# M8340E.net
KiCad netlist of a schematic drawn in EAGLE
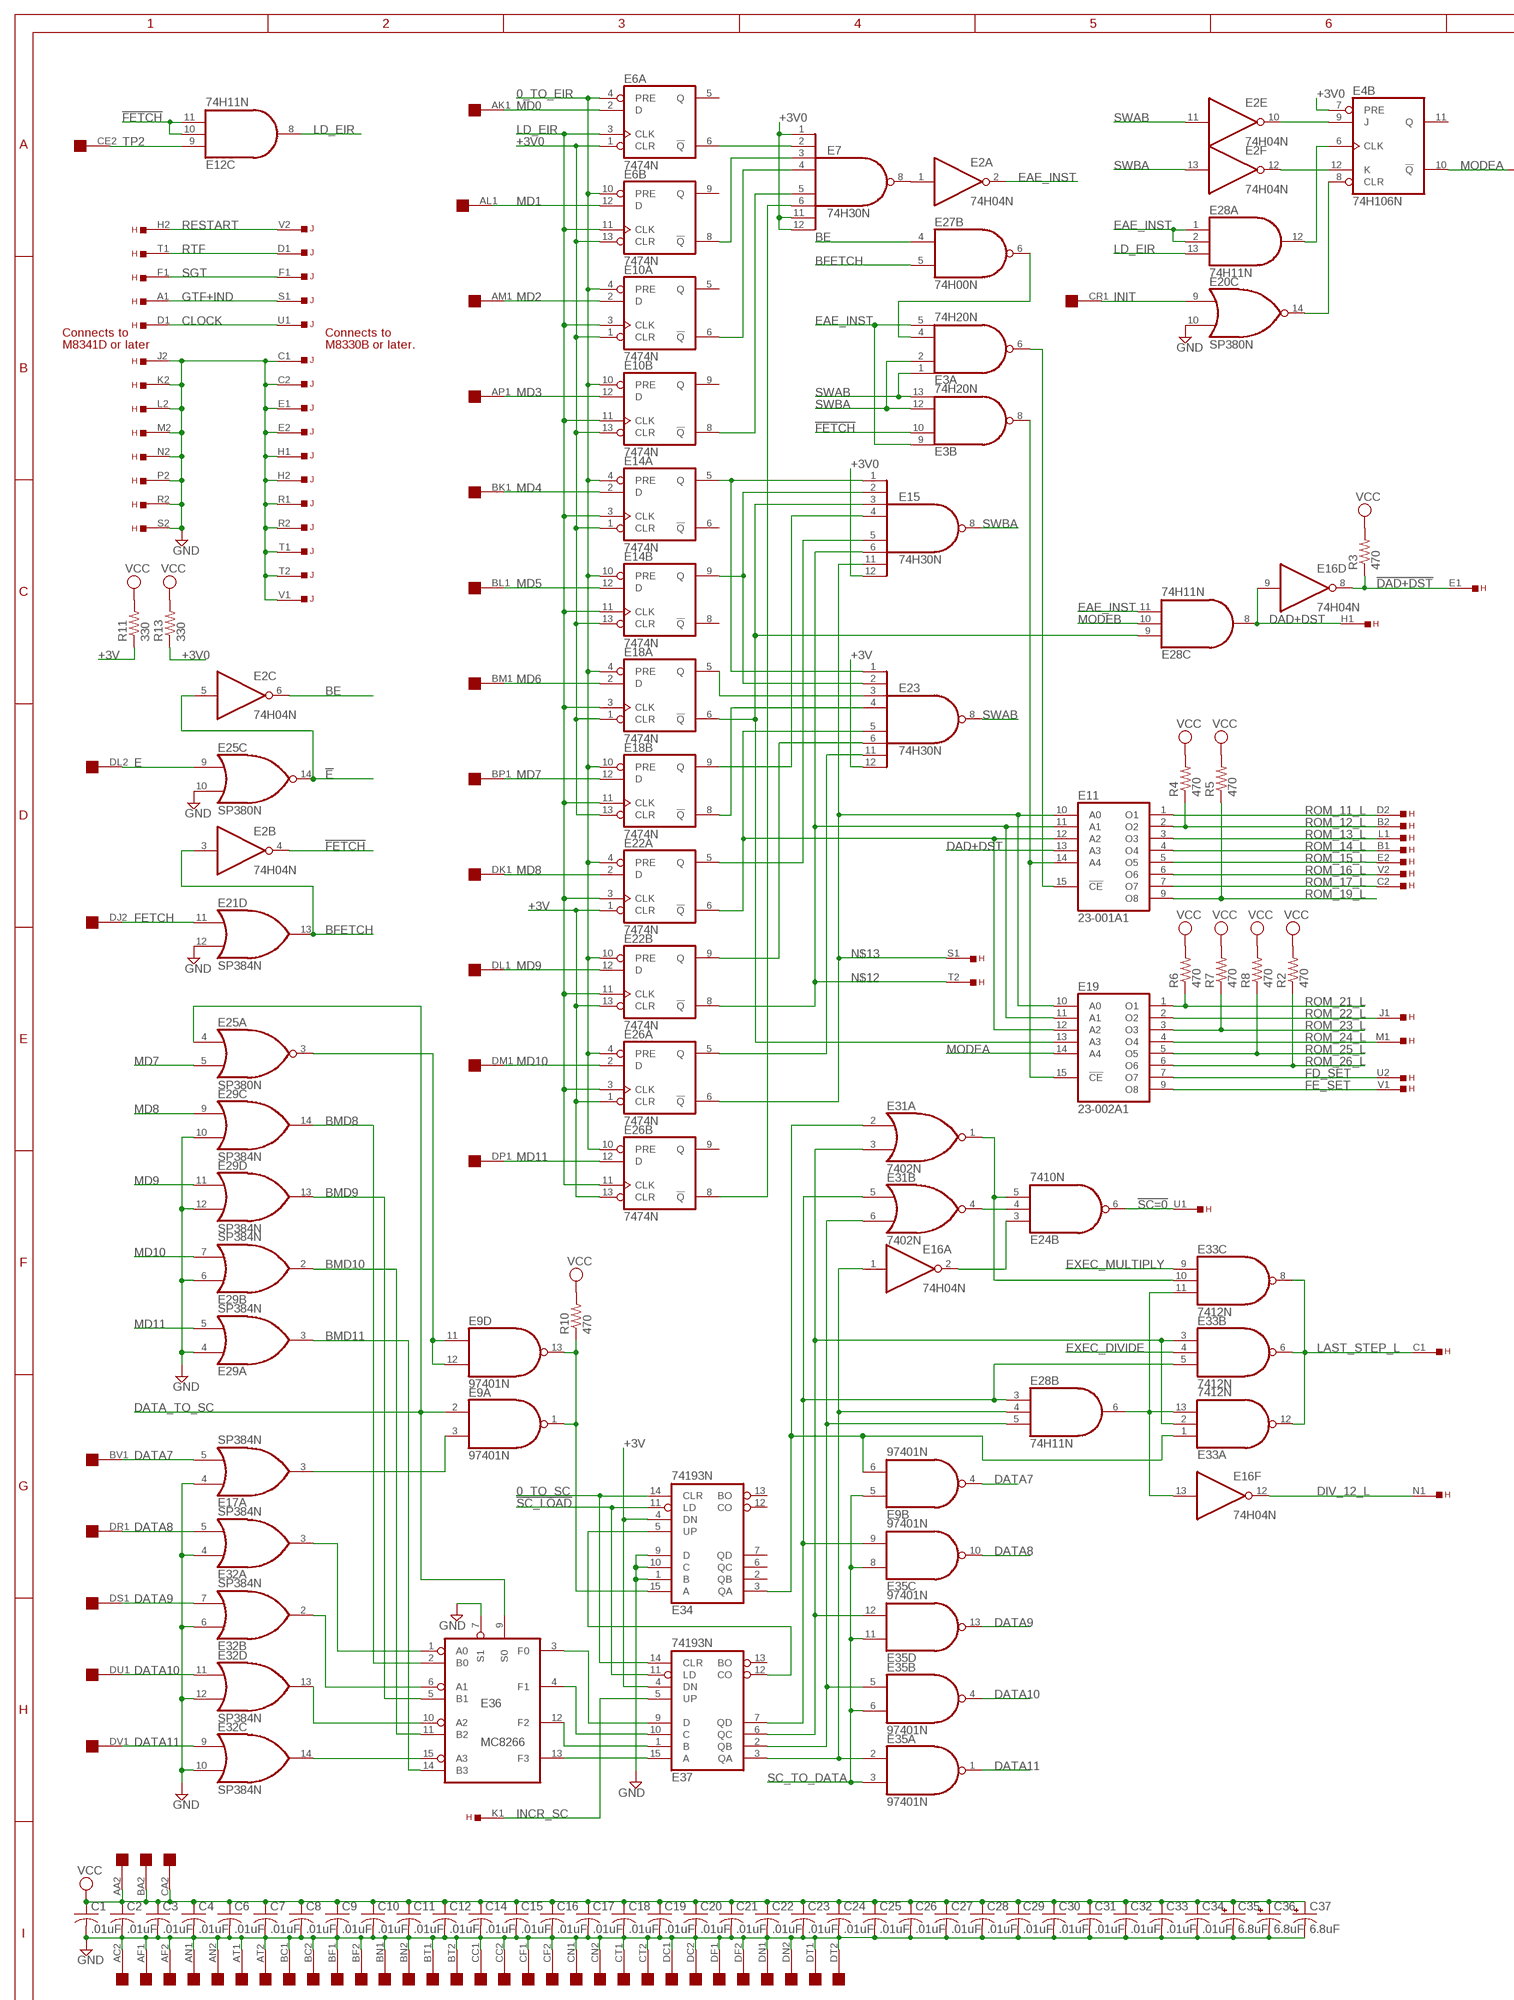
[diagram p0: schematic, sheet 1, part 1 of 2]
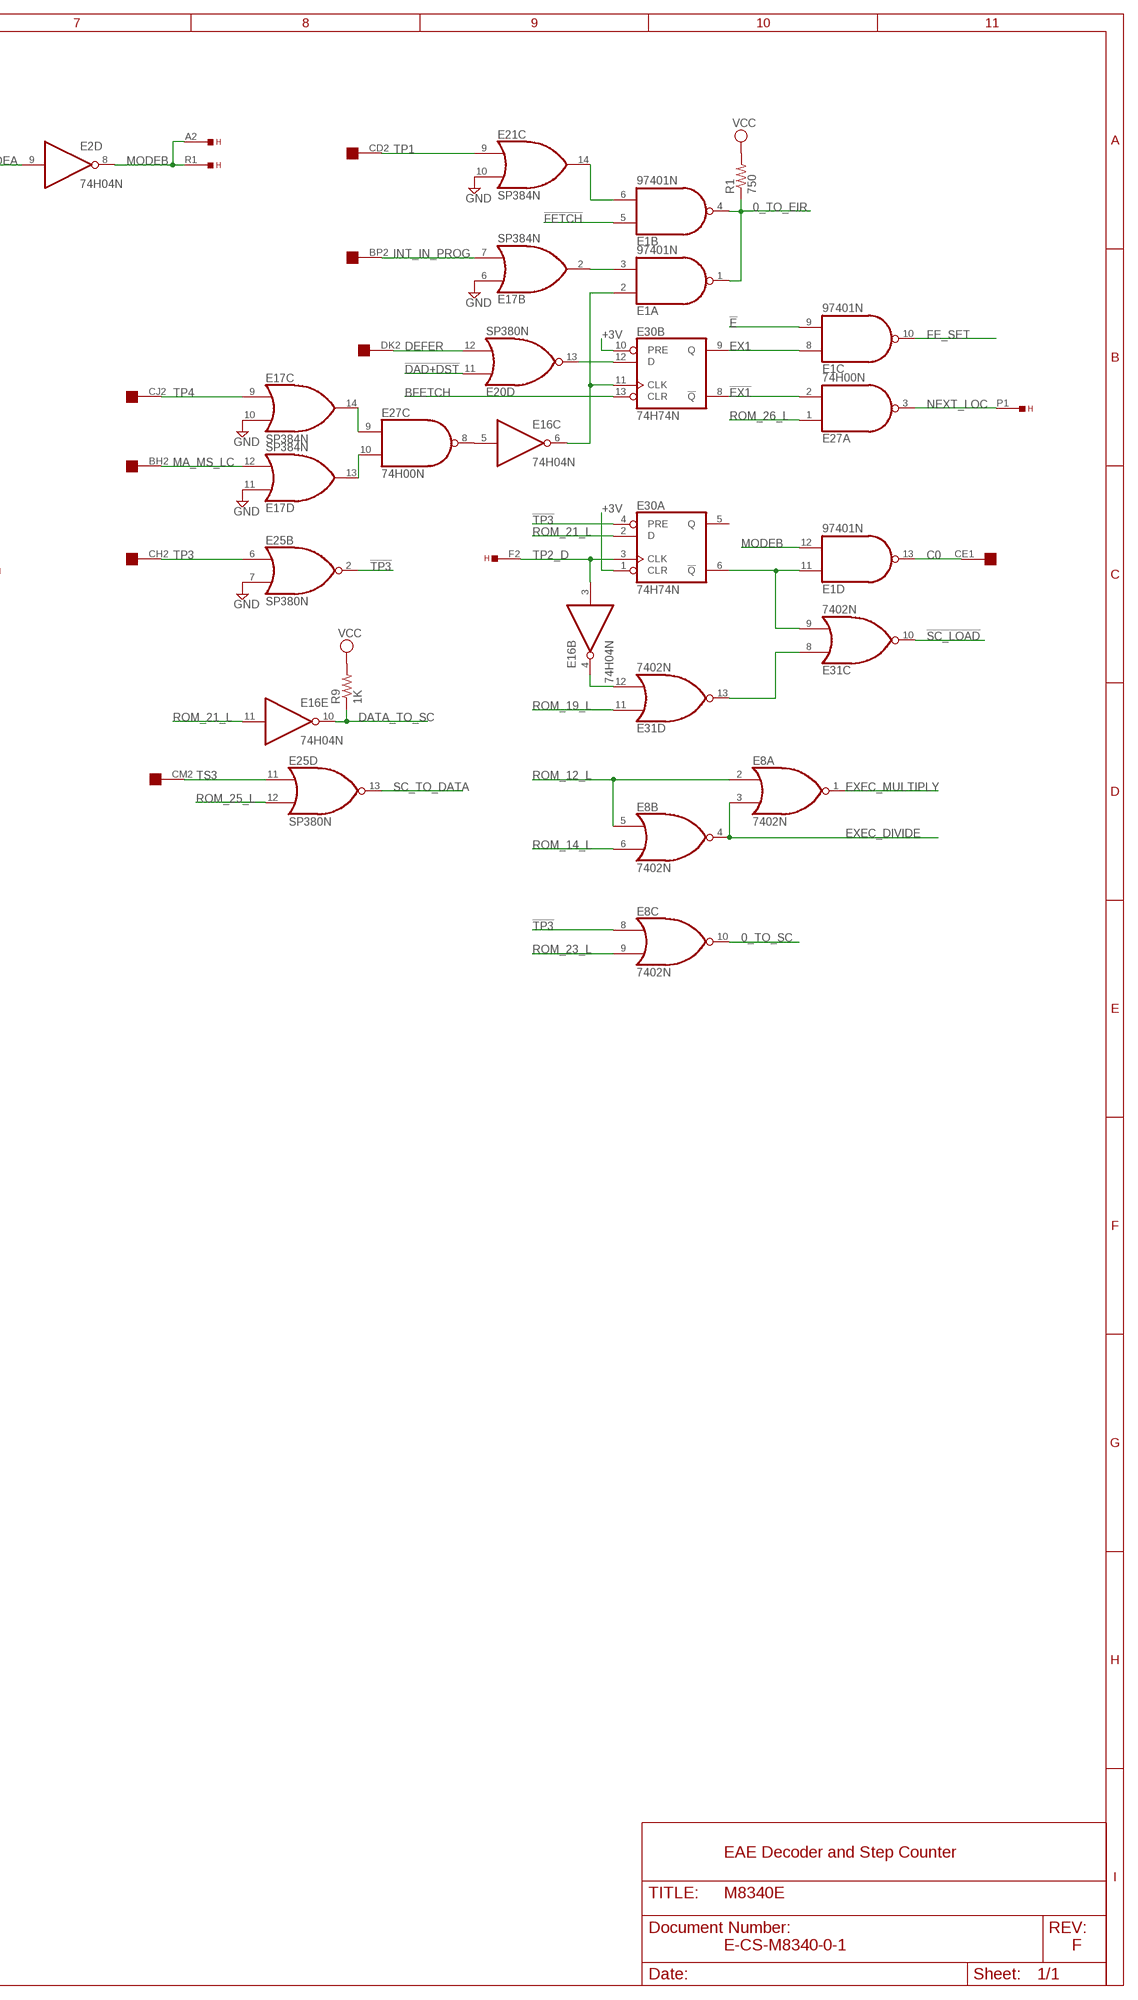
[diagram p1: schematic, sheet 1, part 2 of 2]

(export (version "E")
  (design (tool "Eeschema 10.0.6"))
  (components
    (comp (ref "C1")
      (value ".01uF")
      (footprint "eagle-import:C063-025X075")
      (libsource (lib "eagle-import") (part "C-US"))
    )
    (comp (ref "C2")
      (value ".01uF")
      (footprint "eagle-import:C063-025X075")
      (libsource (lib "eagle-import") (part "C-US"))
    )
    (comp (ref "C3")
      (value ".01uF")
      (footprint "eagle-import:C063-025X075")
      (libsource (lib "eagle-import") (part "C-US"))
    )
    (comp (ref "C4")
      (value ".01uF")
      (footprint "eagle-import:C063-025X075")
      (libsource (lib "eagle-import") (part "C-US"))
    )
    (comp (ref "C6")
      (value ".01uF")
      (footprint "eagle-import:C063-025X075")
      (libsource (lib "eagle-import") (part "C-US"))
    )
    (comp (ref "C7")
      (value ".01uF")
      (footprint "eagle-import:C063-025X075")
      (libsource (lib "eagle-import") (part "C-US"))
    )
    (comp (ref "C8")
      (value ".01uF")
      (footprint "eagle-import:C063-025X075")
      (libsource (lib "eagle-import") (part "C-US"))
    )
    (comp (ref "C9")
      (value ".01uF")
      (footprint "eagle-import:C063-025X075")
      (libsource (lib "eagle-import") (part "C-US"))
    )
    (comp (ref "C10")
      (value ".01uF")
      (footprint "eagle-import:C063-025X075")
      (libsource (lib "eagle-import") (part "C-US"))
    )
    (comp (ref "C11")
      (value ".01uF")
      (footprint "eagle-import:C063-025X075")
      (libsource (lib "eagle-import") (part "C-US"))
    )
    (comp (ref "C12")
      (value ".01uF")
      (footprint "eagle-import:C063-025X075")
      (libsource (lib "eagle-import") (part "C-US"))
    )
    (comp (ref "C14")
      (value ".01uF")
      (footprint "eagle-import:C063-025X075")
      (libsource (lib "eagle-import") (part "C-US"))
    )
    (comp (ref "C15")
      (value ".01uF")
      (footprint "eagle-import:C063-025X075")
      (libsource (lib "eagle-import") (part "C-US"))
    )
    (comp (ref "C16")
      (value ".01uF")
      (footprint "eagle-import:C063-025X075")
      (libsource (lib "eagle-import") (part "C-US"))
    )
    (comp (ref "C17")
      (value ".01uF")
      (footprint "eagle-import:C063-025X075")
      (libsource (lib "eagle-import") (part "C-US"))
    )
    (comp (ref "C18")
      (value ".01uF")
      (footprint "eagle-import:C063-025X075")
      (libsource (lib "eagle-import") (part "C-US"))
    )
    (comp (ref "C19")
      (value ".01uF")
      (footprint "eagle-import:C063-025X075")
      (libsource (lib "eagle-import") (part "C-US"))
    )
    (comp (ref "C20")
      (value ".01uF")
      (footprint "eagle-import:C063-025X075")
      (libsource (lib "eagle-import") (part "C-US"))
    )
    (comp (ref "C21")
      (value ".01uF")
      (footprint "eagle-import:C063-025X075")
      (libsource (lib "eagle-import") (part "C-US"))
    )
    (comp (ref "C22")
      (value ".01uF")
      (footprint "eagle-import:C063-025X075")
      (libsource (lib "eagle-import") (part "C-US"))
    )
    (comp (ref "C23")
      (value ".01uF")
      (footprint "eagle-import:C063-025X075")
      (libsource (lib "eagle-import") (part "C-US"))
    )
    (comp (ref "C24")
      (value ".01uF")
      (footprint "eagle-import:C063-025X075")
      (libsource (lib "eagle-import") (part "C-US"))
    )
    (comp (ref "C25")
      (value ".01uF")
      (footprint "eagle-import:C063-025X075")
      (libsource (lib "eagle-import") (part "C-US"))
    )
    (comp (ref "C26")
      (value ".01uF")
      (footprint "eagle-import:C063-025X075")
      (libsource (lib "eagle-import") (part "C-US"))
    )
    (comp (ref "C27")
      (value ".01uF")
      (footprint "eagle-import:C063-025X075")
      (libsource (lib "eagle-import") (part "C-US"))
    )
    (comp (ref "C28")
      (value ".01uF")
      (footprint "eagle-import:C063-025X075")
      (libsource (lib "eagle-import") (part "C-US"))
    )
    (comp (ref "C29")
      (value ".01uF")
      (footprint "eagle-import:C063-025X075")
      (libsource (lib "eagle-import") (part "C-US"))
    )
    (comp (ref "C30")
      (value ".01uF")
      (footprint "eagle-import:C063-025X075")
      (libsource (lib "eagle-import") (part "C-US"))
    )
    (comp (ref "C31")
      (value ".01uF")
      (footprint "eagle-import:C063-025X075")
      (libsource (lib "eagle-import") (part "C-US"))
    )
    (comp (ref "C32")
      (value ".01uF")
      (footprint "eagle-import:C063-025X075")
      (libsource (lib "eagle-import") (part "C-US"))
    )
    (comp (ref "C33")
      (value ".01uF")
      (footprint "eagle-import:C063-025X075")
      (libsource (lib "eagle-import") (part "C-US"))
    )
    (comp (ref "C34")
      (value ".01uF")
      (footprint "eagle-import:C063-025X075")
      (libsource (lib "eagle-import") (part "C-US"))
    )
    (comp (ref "C35")
      (value "6.8uF")
      (footprint "eagle-import:E12-8")
      (libsource (lib "eagle-import") (part "CPOL-USE20-8AXIAL"))
    )
    (comp (ref "C36")
      (value "6.8uF")
      (footprint "eagle-import:E12-8")
      (libsource (lib "eagle-import") (part "CPOL-USE20-8AXIAL"))
    )
    (comp (ref "C37")
      (value "6.8uF")
      (footprint "eagle-import:E12-8")
      (libsource (lib "eagle-import") (part "CPOL-USE20-8AXIAL"))
    )
    (comp (ref "E1")
      (value "97401N")
      (footprint "eagle-import:DIL14")
      (libsource (lib "eagle-import") (part "7401NLS"))
    )
    (comp (ref "E2")
      (value "74H04N")
      (footprint "eagle-import:DIL14")
      (libsource (lib "eagle-import") (part "7404N"))
    )
    (comp (ref "E3")
      (value "74H20N")
      (footprint "eagle-import:DIL14")
      (libsource (lib "eagle-import") (part "7420N"))
    )
    (comp (ref "E4")
      (value "74H106N")
      (footprint "eagle-import:DIL16")
      (libsource (lib "eagle-import") (part "7476N"))
    )
    (comp (ref "E6")
      (value "7474N")
      (footprint "eagle-import:DIL14")
      (libsource (lib "eagle-import") (part "7474NS"))
    )
    (comp (ref "E7")
      (value "74H30N")
      (footprint "eagle-import:DIL14")
      (libsource (lib "eagle-import") (part "7430N"))
    )
    (comp (ref "E8")
      (value "7402N")
      (footprint "eagle-import:DIL14")
      (libsource (lib "eagle-import") (part "7402N"))
    )
    (comp (ref "E9")
      (value "97401N")
      (footprint "eagle-import:DIL14")
      (libsource (lib "eagle-import") (part "7401NLS"))
    )
    (comp (ref "E10")
      (value "7474N")
      (footprint "eagle-import:DIL14")
      (libsource (lib "eagle-import") (part "7474NS"))
    )
    (comp (ref "E11")
      (value "23-001A1")
      (footprint "eagle-import:DIL16")
      (libsource (lib "eagle-import") (part "5600"))
    )
    (comp (ref "E12")
      (value "74H11N")
      (footprint "eagle-import:DIL14")
      (libsource (lib "eagle-import") (part "7411NS"))
    )
    (comp (ref "E14")
      (value "7474N")
      (footprint "eagle-import:DIL14")
      (libsource (lib "eagle-import") (part "7474NS"))
    )
    (comp (ref "E15")
      (value "74H30N")
      (footprint "eagle-import:DIL14")
      (libsource (lib "eagle-import") (part "7430N"))
    )
    (comp (ref "E16")
      (value "74H04N")
      (footprint "eagle-import:DIL14")
      (libsource (lib "eagle-import") (part "7404N"))
    )
    (comp (ref "E17")
      (value "SP384N")
      (footprint "eagle-import:DIL14")
      (libsource (lib "eagle-import") (part "SP384N"))
    )
    (comp (ref "E18")
      (value "7474N")
      (footprint "eagle-import:DIL14")
      (libsource (lib "eagle-import") (part "7474NS"))
    )
    (comp (ref "E19")
      (value "23-002A1")
      (footprint "eagle-import:DIL16")
      (libsource (lib "eagle-import") (part "5600"))
    )
    (comp (ref "E20")
      (value "SP380N")
      (footprint "eagle-import:DIL14")
      (libsource (lib "eagle-import") (part "SP380N"))
    )
    (comp (ref "E21")
      (value "SP384N")
      (footprint "eagle-import:DIL14")
      (libsource (lib "eagle-import") (part "SP384N"))
    )
    (comp (ref "E22")
      (value "7474N")
      (footprint "eagle-import:DIL14")
      (libsource (lib "eagle-import") (part "7474NS"))
    )
    (comp (ref "E23")
      (value "74H30N")
      (footprint "eagle-import:DIL14")
      (libsource (lib "eagle-import") (part "7430N"))
    )
    (comp (ref "E24")
      (value "7410N")
      (footprint "eagle-import:DIL14")
      (libsource (lib "eagle-import") (part "7410N"))
    )
    (comp (ref "E25")
      (value "SP380N")
      (footprint "eagle-import:DIL14")
      (libsource (lib "eagle-import") (part "SP380N"))
    )
    (comp (ref "E26")
      (value "7474N")
      (footprint "eagle-import:DIL14")
      (libsource (lib "eagle-import") (part "7474NS"))
    )
    (comp (ref "E27")
      (value "74H00N")
      (footprint "eagle-import:DIL14")
      (libsource (lib "eagle-import") (part "7400N"))
    )
    (comp (ref "E28")
      (value "74H11N")
      (footprint "eagle-import:DIL14")
      (libsource (lib "eagle-import") (part "7411NS"))
    )
    (comp (ref "E29")
      (value "SP384N")
      (footprint "eagle-import:DIL14")
      (libsource (lib "eagle-import") (part "SP384N"))
    )
    (comp (ref "E30")
      (value "74H74N")
      (footprint "eagle-import:DIL14")
      (libsource (lib "eagle-import") (part "7474NS"))
    )
    (comp (ref "E31")
      (value "7402N")
      (footprint "eagle-import:DIL14")
      (libsource (lib "eagle-import") (part "7402N"))
    )
    (comp (ref "E32")
      (value "SP384N")
      (footprint "eagle-import:DIL14")
      (libsource (lib "eagle-import") (part "SP384N"))
    )
    (comp (ref "E33")
      (value "7412N")
      (footprint "eagle-import:DIL14")
      (libsource (lib "eagle-import") (part "7412N"))
    )
    (comp (ref "E34")
      (value "74193N")
      (footprint "eagle-import:DIL16")
      (libsource (lib "eagle-import") (part "74193N"))
    )
    (comp (ref "E35")
      (value "97401N")
      (footprint "eagle-import:DIL14")
      (libsource (lib "eagle-import") (part "7401NLS"))
    )
    (comp (ref "E36")
      (value "MC8266")
      (footprint "eagle-import:DIL16")
      (libsource (lib "eagle-import") (part "MC8266"))
    )
    (comp (ref "E37")
      (value "74193N")
      (footprint "eagle-import:DIL16")
      (libsource (lib "eagle-import") (part "74193N"))
    )
    (comp (ref "H")
      (value "EDGE-TOP")
      (footprint "eagle-import:EDGE-CON2")
      (libsource (lib "eagle-import") (part "EDGE-TOP"))
    )
    (comp (ref "J")
      (value "EDGE-TOP")
      (footprint "eagle-import:EDGE-CON2")
      (libsource (lib "eagle-import") (part "EDGE-TOP"))
    )
    (comp (ref "R1")
      (value "750")
      (footprint "eagle-import:0207_10")
      (libsource (lib "eagle-import") (part "R-US_0207/10"))
    )
    (comp (ref "R2")
      (value "470")
      (footprint "eagle-import:0207_10")
      (libsource (lib "eagle-import") (part "R-US_0207/10"))
    )
    (comp (ref "R3")
      (value "470")
      (footprint "eagle-import:0207_10")
      (libsource (lib "eagle-import") (part "R-US_0207/10"))
    )
    (comp (ref "R4")
      (value "470")
      (footprint "eagle-import:0207_10")
      (libsource (lib "eagle-import") (part "R-US_0207/10"))
    )
    (comp (ref "R5")
      (value "470")
      (footprint "eagle-import:0207_10")
      (libsource (lib "eagle-import") (part "R-US_0207/10"))
    )
    (comp (ref "R6")
      (value "470")
      (footprint "eagle-import:0207_10")
      (libsource (lib "eagle-import") (part "R-US_0207/10"))
    )
    (comp (ref "R7")
      (value "470")
      (footprint "eagle-import:0207_10")
      (libsource (lib "eagle-import") (part "R-US_0207/10"))
    )
    (comp (ref "R8")
      (value "470")
      (footprint "eagle-import:0207_10")
      (libsource (lib "eagle-import") (part "R-US_0207/10"))
    )
    (comp (ref "R9")
      (value "1K")
      (footprint "eagle-import:0207_10")
      (libsource (lib "eagle-import") (part "R-US_0207/10"))
    )
    (comp (ref "R10")
      (value "470")
      (footprint "eagle-import:0207_10")
      (libsource (lib "eagle-import") (part "R-US_0207/10"))
    )
    (comp (ref "R11")
      (value "330")
      (footprint "eagle-import:0207_10")
      (libsource (lib "eagle-import") (part "R-US_0207/10"))
    )
    (comp (ref "R13")
      (value "330")
      (footprint "eagle-import:0207_10")
      (libsource (lib "eagle-import") (part "R-US_0207/10"))
    )
    (comp (ref "U$2")
      (value "QUAD")
      (footprint "eagle-import:EDGE-CON8")
      (libsource (lib "eagle-import") (part "QUAD"))
    )
  )
  (nets
    (net (code "1") (name "/+3V") (class "Default")
      (node (ref "E22") (pin "1") (pinfunction "CLR_1") (pintype "input"))
      (node (ref "E22") (pin "13") (pinfunction "CLR_13") (pintype "input"))
      (node (ref "E23") (pin "12") (pinfunction "I7_12") (pintype "input"))
      (node (ref "E26") (pin "1") (pinfunction "CLR_1") (pintype "input"))
      (node (ref "E26") (pin "13") (pinfunction "CLR_13") (pintype "input"))
      (node (ref "E30") (pin "1") (pinfunction "CLR_1") (pintype "input"))
      (node (ref "E30") (pin "10") (pinfunction "PRE_10") (pintype "input"))
      (node (ref "E34") (pin "4") (pinfunction "DN_4") (pintype "input"))
      (node (ref "E37") (pin "4") (pinfunction "DN_4") (pintype "input"))
      (node (ref "R11") (pin "1") (pinfunction "1_1") (pintype "passive"))
    )
    (net (code "2") (name "/+3V0") (class "Default")
      (node (ref "E10") (pin "1") (pinfunction "CLR_1") (pintype "input"))
      (node (ref "E10") (pin "13") (pinfunction "CLR_13") (pintype "input"))
      (node (ref "E14") (pin "1") (pinfunction "CLR_1") (pintype "input"))
      (node (ref "E14") (pin "13") (pinfunction "CLR_13") (pintype "input"))
      (node (ref "E15") (pin "12") (pinfunction "I7_12") (pintype "input"))
      (node (ref "E18") (pin "1") (pinfunction "CLR_1") (pintype "input"))
      (node (ref "E18") (pin "13") (pinfunction "CLR_13") (pintype "input"))
      (node (ref "E4") (pin "7") (pinfunction "PRE_7") (pintype "input"))
      (node (ref "E6") (pin "1") (pinfunction "CLR_1") (pintype "input"))
      (node (ref "E6") (pin "13") (pinfunction "CLR_13") (pintype "input"))
      (node (ref "E7") (pin "1") (pinfunction "I0_1") (pintype "input"))
      (node (ref "E7") (pin "11") (pinfunction "I6_11") (pintype "input"))
      (node (ref "E7") (pin "12") (pinfunction "I7_12") (pintype "input"))
      (node (ref "R13") (pin "1") (pinfunction "1_1") (pintype "passive"))
    )
    (net (code "3") (name "/0_TO_EIR") (class "Default")
      (node (ref "E1") (pin "1") (pinfunction "O_1") (pintype "open_collector"))
      (node (ref "E1") (pin "4") (pinfunction "O_4") (pintype "open_collector"))
      (node (ref "E10") (pin "10") (pinfunction "PRE_10") (pintype "input"))
      (node (ref "E10") (pin "4") (pinfunction "PRE_4") (pintype "input"))
      (node (ref "E14") (pin "10") (pinfunction "PRE_10") (pintype "input"))
      (node (ref "E14") (pin "4") (pinfunction "PRE_4") (pintype "input"))
      (node (ref "E18") (pin "10") (pinfunction "PRE_10") (pintype "input"))
      (node (ref "E18") (pin "4") (pinfunction "PRE_4") (pintype "input"))
      (node (ref "E22") (pin "10") (pinfunction "PRE_10") (pintype "input"))
      (node (ref "E22") (pin "4") (pinfunction "PRE_4") (pintype "input"))
      (node (ref "E26") (pin "10") (pinfunction "PRE_10") (pintype "input"))
      (node (ref "E26") (pin "4") (pinfunction "PRE_4") (pintype "input"))
      (node (ref "E6") (pin "10") (pinfunction "PRE_10") (pintype "input"))
      (node (ref "E6") (pin "4") (pinfunction "PRE_4") (pintype "input"))
      (node (ref "R1") (pin "1") (pinfunction "1_1") (pintype "passive"))
    )
    (net (code "4") (name "/0_TO_SC") (class "Default")
      (node (ref "E34") (pin "14") (pinfunction "CLR_14") (pintype "input"))
      (node (ref "E37") (pin "14") (pinfunction "CLR_14") (pintype "input"))
      (node (ref "E8") (pin "10") (pinfunction "O_10") (pintype "output"))
    )
    (net (code "5") (name "/BE") (class "Default")
      (node (ref "E2") (pin "6") (pinfunction "O_6") (pintype "output"))
      (node (ref "E27") (pin "4") (pinfunction "I0_4") (pintype "input"))
    )
    (net (code "6") (name "/BFETCH") (class "Default")
      (node (ref "E2") (pin "3") (pinfunction "I_3") (pintype "input"))
      (node (ref "E21") (pin "13") (pinfunction "O_13") (pintype "output"))
      (node (ref "E27") (pin "5") (pinfunction "I1_5") (pintype "input"))
      (node (ref "E30") (pin "13") (pinfunction "CLR_13") (pintype "input"))
    )
    (net (code "7") (name "/BMD8") (class "Default")
      (node (ref "E29") (pin "14") (pinfunction "O_14") (pintype "output"))
      (node (ref "E36") (pin "2") (pinfunction "B0_2") (pintype "input"))
    )
    (net (code "8") (name "/BMD9") (class "Default")
      (node (ref "E29") (pin "13") (pinfunction "O_13") (pintype "output"))
      (node (ref "E36") (pin "5") (pinfunction "B1_5") (pintype "input"))
    )
    (net (code "9") (name "/BMD10") (class "Default")
      (node (ref "E29") (pin "2") (pinfunction "O_2") (pintype "output"))
      (node (ref "E36") (pin "11") (pinfunction "B2_11") (pintype "input"))
    )
    (net (code "10") (name "/BMD11") (class "Default")
      (node (ref "E29") (pin "3") (pinfunction "O_3") (pintype "output"))
      (node (ref "E36") (pin "14") (pinfunction "B3_14") (pintype "input"))
    )
    (net (code "11") (name "/C0") (class "Default")
      (node (ref "E1") (pin "13") (pinfunction "O_13") (pintype "open_collector"))
      (node (ref "U$2") (pin "CE1") (pinfunction "1_CE1") (pintype "bidirectional"))
    )
    (net (code "12") (name "/CLOCK") (class "Default")
      (node (ref "H") (pin "D1") (pinfunction "P_D1") (pintype "passive"))
      (node (ref "J") (pin "U1") (pinfunction "P_U1") (pintype "passive"))
    )
    (net (code "13") (name "/DAD+DST") (class "Default")
      (node (ref "E11") (pin "13") (pinfunction "A3_13") (pintype "input"))
      (node (ref "E16") (pin "9") (pinfunction "I_9") (pintype "input"))
      (node (ref "E28") (pin "8") (pinfunction "O_8") (pintype "output"))
      (node (ref "H") (pin "H1") (pinfunction "P_H1") (pintype "passive"))
    )
    (net (code "14") (name "/DATA7") (class "Default")
      (node (ref "E17") (pin "5") (pinfunction "I1_5") (pintype "input"))
      (node (ref "E9") (pin "4") (pinfunction "O_4") (pintype "open_collector"))
      (node (ref "U$2") (pin "BV1") (pinfunction "1_BV1") (pintype "bidirectional"))
    )
    (net (code "15") (name "/DATA8") (class "Default")
      (node (ref "E32") (pin "5") (pinfunction "I1_5") (pintype "input"))
      (node (ref "E35") (pin "10") (pinfunction "O_10") (pintype "open_collector"))
      (node (ref "U$2") (pin "DR1") (pinfunction "1_DR1") (pintype "bidirectional"))
    )
    (net (code "16") (name "/DATA9") (class "Default")
      (node (ref "E32") (pin "7") (pinfunction "I1_7") (pintype "input"))
      (node (ref "E35") (pin "13") (pinfunction "O_13") (pintype "open_collector"))
      (node (ref "U$2") (pin "DS1") (pinfunction "1_DS1") (pintype "bidirectional"))
    )
    (net (code "17") (name "/DATA10") (class "Default")
      (node (ref "E32") (pin "11") (pinfunction "I0_11") (pintype "input"))
      (node (ref "E35") (pin "4") (pinfunction "O_4") (pintype "open_collector"))
      (node (ref "U$2") (pin "DU1") (pinfunction "1_DU1") (pintype "bidirectional"))
    )
    (net (code "18") (name "/DATA11") (class "Default")
      (node (ref "E32") (pin "9") (pinfunction "I0_9") (pintype "input"))
      (node (ref "E35") (pin "1") (pinfunction "O_1") (pintype "open_collector"))
      (node (ref "U$2") (pin "DV1") (pinfunction "1_DV1") (pintype "bidirectional"))
    )
    (net (code "19") (name "/DATA_TO_SC") (class "Default")
      (node (ref "E16") (pin "10") (pinfunction "O_10") (pintype "output"))
      (node (ref "E25") (pin "4") (pinfunction "I0_4") (pintype "input"))
      (node (ref "E36") (pin "9") (pinfunction "S0_9") (pintype "input"))
      (node (ref "E9") (pin "2") (pinfunction "I0_2") (pintype "input"))
      (node (ref "R9") (pin "1") (pinfunction "1_1") (pintype "passive"))
    )
    (net (code "20") (name "/DEFER") (class "Default")
      (node (ref "E20") (pin "12") (pinfunction "I1_12") (pintype "input"))
      (node (ref "U$2") (pin "DK2") (pinfunction "1_DK2") (pintype "bidirectional"))
    )
    (net (code "21") (name "/DIV_12_L") (class "Default")
      (node (ref "E16") (pin "12") (pinfunction "O_12") (pintype "output"))
      (node (ref "H") (pin "N1") (pinfunction "P_N1") (pintype "passive"))
    )
    (net (code "22") (name "/E") (class "Default")
      (node (ref "E25") (pin "9") (pinfunction "I0_9") (pintype "input"))
      (node (ref "U$2") (pin "DL2") (pinfunction "1_DL2") (pintype "bidirectional"))
    )
    (net (code "23") (name "/EAE_INST") (class "Default")
      (node (ref "E2") (pin "2") (pinfunction "O_2") (pintype "output"))
      (node (ref "E28") (pin "1") (pinfunction "I0_1") (pintype "input"))
      (node (ref "E28") (pin "11") (pinfunction "I2_11") (pintype "input"))
      (node (ref "E28") (pin "2") (pinfunction "I1_2") (pintype "input"))
      (node (ref "E3") (pin "5") (pinfunction "I3_5") (pintype "input"))
      (node (ref "E3") (pin "9") (pinfunction "I0_9") (pintype "input"))
    )
    (net (code "24") (name "/EX1") (class "Default")
      (node (ref "E1") (pin "8") (pinfunction "I0_8") (pintype "input"))
      (node (ref "E30") (pin "9") (pinfunction "Q_9") (pintype "output"))
    )
    (net (code "25") (name "/EXEC_DIVIDE") (class "Default")
      (node (ref "E33") (pin "4") (pinfunction "I1_4") (pintype "input"))
      (node (ref "E8") (pin "3") (pinfunction "I1_3") (pintype "input"))
      (node (ref "E8") (pin "4") (pinfunction "O_4") (pintype "output"))
    )
    (net (code "26") (name "/EXEC_MULTIPLY") (class "Default")
      (node (ref "E33") (pin "9") (pinfunction "I0_9") (pintype "input"))
      (node (ref "E8") (pin "1") (pinfunction "O_1") (pintype "output"))
    )
    (net (code "27") (name "/FD_SET") (class "Default")
      (node (ref "E19") (pin "7") (pinfunction "O7_7") (pintype "open_collector"))
      (node (ref "H") (pin "U2") (pinfunction "P_U2") (pintype "passive"))
    )
    (net (code "28") (name "/FETCH") (class "Default")
      (node (ref "E21") (pin "11") (pinfunction "I0_11") (pintype "input"))
      (node (ref "U$2") (pin "DJ2") (pinfunction "1_DJ2") (pintype "bidirectional"))
    )
    (net (code "29") (name "/FE_SET") (class "Default")
      (node (ref "E1") (pin "10") (pinfunction "O_10") (pintype "open_collector"))
      (node (ref "E19") (pin "9") (pinfunction "O8_9") (pintype "open_collector"))
      (node (ref "H") (pin "V1") (pinfunction "P_V1") (pintype "passive"))
    )
    (net (code "30") (name "/GTF+IND") (class "Default")
      (node (ref "H") (pin "A1") (pinfunction "P_A1") (pintype "passive"))
      (node (ref "J") (pin "S1") (pinfunction "P_S1") (pintype "passive"))
    )
    (net (code "31") (name "/INCR_SC") (class "Default")
      (node (ref "E37") (pin "5") (pinfunction "UP_5") (pintype "input"))
      (node (ref "H") (pin "K1") (pinfunction "P_K1") (pintype "passive"))
    )
    (net (code "32") (name "/INIT") (class "Default")
      (node (ref "E20") (pin "9") (pinfunction "I0_9") (pintype "input"))
      (node (ref "U$2") (pin "CR1") (pinfunction "1_CR1") (pintype "bidirectional"))
    )
    (net (code "33") (name "/INT_IN_PROG") (class "Default")
      (node (ref "E17") (pin "7") (pinfunction "I1_7") (pintype "input"))
      (node (ref "U$2") (pin "BP2") (pinfunction "1_BP2") (pintype "bidirectional"))
    )
    (net (code "34") (name "/LAST_STEP_L") (class "Default")
      (node (ref "E33") (pin "12") (pinfunction "O_12") (pintype "open_collector"))
      (node (ref "E33") (pin "6") (pinfunction "O_6") (pintype "open_collector"))
      (node (ref "E33") (pin "8") (pinfunction "O_8") (pintype "open_collector"))
      (node (ref "H") (pin "C1") (pinfunction "P_C1") (pintype "passive"))
    )
    (net (code "35") (name "/LD_EIR") (class "Default")
      (node (ref "E10") (pin "11") (pinfunction "CLK_11") (pintype "input"))
      (node (ref "E10") (pin "3") (pinfunction "CLK_3") (pintype "input"))
      (node (ref "E12") (pin "8") (pinfunction "O_8") (pintype "output"))
      (node (ref "E14") (pin "11") (pinfunction "CLK_11") (pintype "input"))
      (node (ref "E14") (pin "3") (pinfunction "CLK_3") (pintype "input"))
      (node (ref "E18") (pin "11") (pinfunction "CLK_11") (pintype "input"))
      (node (ref "E18") (pin "3") (pinfunction "CLK_3") (pintype "input"))
      (node (ref "E22") (pin "11") (pinfunction "CLK_11") (pintype "input"))
      (node (ref "E22") (pin "3") (pinfunction "CLK_3") (pintype "input"))
      (node (ref "E26") (pin "11") (pinfunction "CLK_11") (pintype "input"))
      (node (ref "E26") (pin "3") (pinfunction "CLK_3") (pintype "input"))
      (node (ref "E28") (pin "13") (pinfunction "I2_13") (pintype "input"))
      (node (ref "E6") (pin "11") (pinfunction "CLK_11") (pintype "input"))
      (node (ref "E6") (pin "3") (pinfunction "CLK_3") (pintype "input"))
    )
    (net (code "36") (name "/MA_MS_LC") (class "Default")
      (node (ref "E17") (pin "12") (pinfunction "I1_12") (pintype "input"))
      (node (ref "U$2") (pin "BH2") (pinfunction "1_BH2") (pintype "bidirectional"))
    )
    (net (code "37") (name "/MD0") (class "Default")
      (node (ref "E6") (pin "2") (pinfunction "D_2") (pintype "input"))
      (node (ref "U$2") (pin "AK1") (pinfunction "1_AK1") (pintype "bidirectional"))
    )
    (net (code "38") (name "/MD1") (class "Default")
      (node (ref "E6") (pin "12") (pinfunction "D_12") (pintype "input"))
      (node (ref "U$2") (pin "AL1") (pinfunction "1_AL1") (pintype "bidirectional"))
    )
    (net (code "39") (name "/MD2") (class "Default")
      (node (ref "E10") (pin "2") (pinfunction "D_2") (pintype "input"))
      (node (ref "U$2") (pin "AM1") (pinfunction "1_AM1") (pintype "bidirectional"))
    )
    (net (code "40") (name "/MD3") (class "Default")
      (node (ref "E10") (pin "12") (pinfunction "D_12") (pintype "input"))
      (node (ref "U$2") (pin "AP1") (pinfunction "1_AP1") (pintype "bidirectional"))
    )
    (net (code "41") (name "/MD4") (class "Default")
      (node (ref "E14") (pin "2") (pinfunction "D_2") (pintype "input"))
      (node (ref "U$2") (pin "BK1") (pinfunction "1_BK1") (pintype "bidirectional"))
    )
    (net (code "42") (name "/MD5") (class "Default")
      (node (ref "E14") (pin "12") (pinfunction "D_12") (pintype "input"))
      (node (ref "U$2") (pin "BL1") (pinfunction "1_BL1") (pintype "bidirectional"))
    )
    (net (code "43") (name "/MD6") (class "Default")
      (node (ref "E18") (pin "2") (pinfunction "D_2") (pintype "input"))
      (node (ref "U$2") (pin "BM1") (pinfunction "1_BM1") (pintype "bidirectional"))
    )
    (net (code "44") (name "/MD7") (class "Default")
      (node (ref "E18") (pin "12") (pinfunction "D_12") (pintype "input"))
      (node (ref "E25") (pin "5") (pinfunction "I1_5") (pintype "input"))
      (node (ref "U$2") (pin "BP1") (pinfunction "1_BP1") (pintype "bidirectional"))
    )
    (net (code "45") (name "/MD8") (class "Default")
      (node (ref "E22") (pin "2") (pinfunction "D_2") (pintype "input"))
      (node (ref "E29") (pin "9") (pinfunction "I0_9") (pintype "input"))
      (node (ref "U$2") (pin "DK1") (pinfunction "1_DK1") (pintype "bidirectional"))
    )
    (net (code "46") (name "/MD9") (class "Default")
      (node (ref "E22") (pin "12") (pinfunction "D_12") (pintype "input"))
      (node (ref "E29") (pin "11") (pinfunction "I0_11") (pintype "input"))
      (node (ref "U$2") (pin "DL1") (pinfunction "1_DL1") (pintype "bidirectional"))
    )
    (net (code "47") (name "/MD10") (class "Default")
      (node (ref "E26") (pin "2") (pinfunction "D_2") (pintype "input"))
      (node (ref "E29") (pin "7") (pinfunction "I1_7") (pintype "input"))
      (node (ref "U$2") (pin "DM1") (pinfunction "1_DM1") (pintype "bidirectional"))
    )
    (net (code "48") (name "/MD11") (class "Default")
      (node (ref "E26") (pin "12") (pinfunction "D_12") (pintype "input"))
      (node (ref "E29") (pin "5") (pinfunction "I1_5") (pintype "input"))
      (node (ref "U$2") (pin "DP1") (pinfunction "1_DP1") (pintype "bidirectional"))
    )
    (net (code "49") (name "/MODEA") (class "Default")
      (node (ref "E19") (pin "14") (pinfunction "A4_14") (pintype "input"))
      (node (ref "E2") (pin "9") (pinfunction "I_9") (pintype "input"))
      (node (ref "E4") (pin "10") (pinfunction "~{Q}_10") (pintype "output"))
    )
    (net (code "50") (name "/MODEB") (class "Default")
      (node (ref "E1") (pin "12") (pinfunction "I1_12") (pintype "input"))
      (node (ref "E2") (pin "8") (pinfunction "O_8") (pintype "output"))
      (node (ref "E28") (pin "10") (pinfunction "I1_10") (pintype "input"))
      (node (ref "H") (pin "A2") (pinfunction "P_A2") (pintype "passive"))
      (node (ref "H") (pin "R1") (pinfunction "P_R1") (pintype "passive"))
    )
    (net (code "51") (name "/N$12") (class "Default")
      (node (ref "E11") (pin "11") (pinfunction "A1_11") (pintype "input"))
      (node (ref "E15") (pin "6") (pinfunction "I5_6") (pintype "input"))
      (node (ref "E19") (pin "11") (pinfunction "A1_11") (pintype "input"))
      (node (ref "E22") (pin "8") (pinfunction "~{Q}_8") (pintype "output"))
      (node (ref "H") (pin "T2") (pinfunction "P_T2") (pintype "passive"))
    )
    (net (code "52") (name "/N$13") (class "Default")
      (node (ref "E11") (pin "10") (pinfunction "A0_10") (pintype "input"))
      (node (ref "E15") (pin "11") (pinfunction "I6_11") (pintype "input"))
      (node (ref "E19") (pin "10") (pinfunction "A0_10") (pintype "input"))
      (node (ref "E26") (pin "6") (pinfunction "~{Q}_6") (pintype "output"))
      (node (ref "H") (pin "S1") (pinfunction "P_S1") (pintype "passive"))
    )
    (net (code "53") (name "/NEXT_LOC") (class "Default")
      (node (ref "E27") (pin "3") (pinfunction "O_3") (pintype "output"))
      (node (ref "H") (pin "P1") (pinfunction "P_P1") (pintype "passive"))
    )
    (net (code "54") (name "/RESTART") (class "Default")
      (node (ref "H") (pin "H2") (pinfunction "P_H2") (pintype "passive"))
      (node (ref "J") (pin "V2") (pinfunction "P_V2") (pintype "passive"))
    )
    (net (code "55") (name "/ROM_11_L") (class "Default")
      (node (ref "E11") (pin "1") (pinfunction "O1_1") (pintype "open_collector"))
      (node (ref "H") (pin "D2") (pinfunction "P_D2") (pintype "passive"))
    )
    (net (code "56") (name "/ROM_12_L") (class "Default")
      (node (ref "E11") (pin "2") (pinfunction "O2_2") (pintype "open_collector"))
      (node (ref "E8") (pin "2") (pinfunction "I0_2") (pintype "input"))
      (node (ref "E8") (pin "5") (pinfunction "I0_5") (pintype "input"))
      (node (ref "H") (pin "B2") (pinfunction "P_B2") (pintype "passive"))
      (node (ref "R4") (pin "1") (pinfunction "1_1") (pintype "passive"))
    )
    (net (code "57") (name "/ROM_13_L") (class "Default")
      (node (ref "E11") (pin "3") (pinfunction "O3_3") (pintype "open_collector"))
      (node (ref "H") (pin "L1") (pinfunction "P_L1") (pintype "passive"))
    )
    (net (code "58") (name "/ROM_14_L") (class "Default")
      (node (ref "E11") (pin "4") (pinfunction "O4_4") (pintype "open_collector"))
      (node (ref "E8") (pin "6") (pinfunction "I1_6") (pintype "input"))
      (node (ref "H") (pin "B1") (pinfunction "P_B1") (pintype "passive"))
    )
    (net (code "59") (name "/ROM_15_L") (class "Default")
      (node (ref "E11") (pin "5") (pinfunction "O5_5") (pintype "open_collector"))
      (node (ref "H") (pin "E2") (pinfunction "P_E2") (pintype "passive"))
    )
    (net (code "60") (name "/ROM_16_L") (class "Default")
      (node (ref "E11") (pin "6") (pinfunction "O6_6") (pintype "open_collector"))
      (node (ref "H") (pin "V2") (pinfunction "P_V2") (pintype "passive"))
    )
    (net (code "61") (name "/ROM_17_L") (class "Default")
      (node (ref "E11") (pin "7") (pinfunction "O7_7") (pintype "open_collector"))
      (node (ref "H") (pin "C2") (pinfunction "P_C2") (pintype "passive"))
    )
    (net (code "62") (name "/ROM_19_L") (class "Default")
      (node (ref "E11") (pin "9") (pinfunction "O8_9") (pintype "open_collector"))
      (node (ref "E31") (pin "11") (pinfunction "I0_11") (pintype "input"))
      (node (ref "R5") (pin "1") (pinfunction "1_1") (pintype "passive"))
    )
    (net (code "63") (name "/ROM_21_L") (class "Default")
      (node (ref "E16") (pin "11") (pinfunction "I_11") (pintype "input"))
      (node (ref "E19") (pin "1") (pinfunction "O1_1") (pintype "open_collector"))
      (node (ref "E30") (pin "2") (pinfunction "D_2") (pintype "input"))
      (node (ref "R6") (pin "1") (pinfunction "1_1") (pintype "passive"))
    )
    (net (code "64") (name "/ROM_22_L") (class "Default")
      (node (ref "E19") (pin "2") (pinfunction "O2_2") (pintype "open_collector"))
      (node (ref "H") (pin "J1") (pinfunction "P_J1") (pintype "passive"))
    )
    (net (code "65") (name "/ROM_23_L") (class "Default")
      (node (ref "E19") (pin "3") (pinfunction "O3_3") (pintype "open_collector"))
      (node (ref "E8") (pin "9") (pinfunction "I1_9") (pintype "input"))
      (node (ref "R7") (pin "1") (pinfunction "1_1") (pintype "passive"))
    )
    (net (code "66") (name "/ROM_24_L") (class "Default")
      (node (ref "E19") (pin "4") (pinfunction "O4_4") (pintype "open_collector"))
      (node (ref "H") (pin "M1") (pinfunction "P_M1") (pintype "passive"))
    )
    (net (code "67") (name "/ROM_25_L") (class "Default")
      (node (ref "E19") (pin "5") (pinfunction "O5_5") (pintype "open_collector"))
      (node (ref "E25") (pin "12") (pinfunction "I1_12") (pintype "input"))
      (node (ref "R8") (pin "1") (pinfunction "1_1") (pintype "passive"))
    )
    (net (code "68") (name "/ROM_26_L") (class "Default")
      (node (ref "E19") (pin "6") (pinfunction "O6_6") (pintype "open_collector"))
      (node (ref "E27") (pin "1") (pinfunction "I0_1") (pintype "input"))
      (node (ref "R2") (pin "1") (pinfunction "1_1") (pintype "passive"))
    )
    (net (code "69") (name "/RTF") (class "Default")
      (node (ref "H") (pin "T1") (pinfunction "P_T1") (pintype "passive"))
      (node (ref "J") (pin "D1") (pinfunction "P_D1") (pintype "passive"))
    )
    (net (code "70") (name "/SC_TO_DATA") (class "Default")
      (node (ref "E25") (pin "13") (pinfunction "O_13") (pintype "output"))
      (node (ref "E35") (pin "11") (pinfunction "I0_11") (pintype "input"))
      (node (ref "E35") (pin "3") (pinfunction "I1_3") (pintype "input"))
      (node (ref "E35") (pin "6") (pinfunction "I1_6") (pintype "input"))
      (node (ref "E35") (pin "8") (pinfunction "I0_8") (pintype "input"))
      (node (ref "E9") (pin "5") (pinfunction "I0_5") (pintype "input"))
    )
    (net (code "71") (name "/SGT") (class "Default")
      (node (ref "H") (pin "F1") (pinfunction "P_F1") (pintype "passive"))
      (node (ref "J") (pin "F1") (pinfunction "P_F1") (pintype "passive"))
    )
    (net (code "72") (name "/SWAB") (class "Default")
      (node (ref "E2") (pin "11") (pinfunction "I_11") (pintype "input"))
      (node (ref "E23") (pin "8") (pinfunction "O_8") (pintype "output"))
      (node (ref "E3") (pin "1") (pinfunction "I0_1") (pintype "input"))
      (node (ref "E3") (pin "13") (pinfunction "I3_13") (pintype "input"))
    )
    (net (code "73") (name "/SWBA") (class "Default")
      (node (ref "E15") (pin "8") (pinfunction "O_8") (pintype "output"))
      (node (ref "E2") (pin "13") (pinfunction "I_13") (pintype "input"))
      (node (ref "E3") (pin "12") (pinfunction "I2_12") (pintype "input"))
      (node (ref "E3") (pin "2") (pinfunction "I1_2") (pintype "input"))
    )
    (net (code "74") (name "/TP1") (class "Default")
      (node (ref "E21") (pin "9") (pinfunction "I0_9") (pintype "input"))
      (node (ref "U$2") (pin "CD2") (pinfunction "1_CD2") (pintype "bidirectional"))
    )
    (net (code "75") (name "/TP2") (class "Default")
      (node (ref "E12") (pin "9") (pinfunction "I0_9") (pintype "input"))
      (node (ref "U$2") (pin "CE2") (pinfunction "1_CE2") (pintype "bidirectional"))
    )
    (net (code "76") (name "/TP2_D") (class "Default")
      (node (ref "E16") (pin "3") (pinfunction "I_3") (pintype "input"))
      (node (ref "E30") (pin "3") (pinfunction "CLK_3") (pintype "input"))
      (node (ref "H") (pin "F2") (pinfunction "P_F2") (pintype "passive"))
    )
    (net (code "77") (name "/TP3") (class "Default")
      (node (ref "E25") (pin "6") (pinfunction "I0_6") (pintype "input"))
      (node (ref "U$2") (pin "CH2") (pinfunction "1_CH2") (pintype "bidirectional"))
    )
    (net (code "78") (name "/TP4") (class "Default")
      (node (ref "E17") (pin "9") (pinfunction "I0_9") (pintype "input"))
      (node (ref "U$2") (pin "CJ2") (pinfunction "1_CJ2") (pintype "bidirectional"))
    )
    (net (code "79") (name "/TS3") (class "Default")
      (node (ref "E25") (pin "11") (pinfunction "I0_11") (pintype "input"))
      (node (ref "U$2") (pin "CM2") (pinfunction "1_CM2") (pintype "bidirectional"))
    )
    (net (code "80") (name "/~{DAD+DST}") (class "Default")
      (node (ref "E16") (pin "8") (pinfunction "O_8") (pintype "output"))
      (node (ref "E20") (pin "11") (pinfunction "I0_11") (pintype "input"))
      (node (ref "H") (pin "E1") (pinfunction "P_E1") (pintype "passive"))
      (node (ref "R3") (pin "1") (pinfunction "1_1") (pintype "passive"))
    )
    (net (code "81") (name "/~{EX1}") (class "Default")
      (node (ref "E27") (pin "2") (pinfunction "I1_2") (pintype "input"))
      (node (ref "E30") (pin "8") (pinfunction "~{Q}_8") (pintype "output"))
    )
    (net (code "82") (name "/~{E}") (class "Default")
      (node (ref "E1") (pin "9") (pinfunction "I1_9") (pintype "input"))
      (node (ref "E2") (pin "5") (pinfunction "I_5") (pintype "input"))
      (node (ref "E25") (pin "14") (pinfunction "O_14") (pintype "output"))
    )
    (net (code "83") (name "/~{FETCH}") (class "Default")
      (node (ref "E1") (pin "5") (pinfunction "I0_5") (pintype "input"))
      (node (ref "E12") (pin "10") (pinfunction "I1_10") (pintype "input"))
      (node (ref "E12") (pin "11") (pinfunction "I2_11") (pintype "input"))
      (node (ref "E2") (pin "4") (pinfunction "O_4") (pintype "output"))
      (node (ref "E3") (pin "10") (pinfunction "I1_10") (pintype "input"))
    )
    (net (code "84") (name "/~{SC=0}") (class "Default")
      (node (ref "E24") (pin "6") (pinfunction "O_6") (pintype "output"))
      (node (ref "H") (pin "U1") (pinfunction "P_U1") (pintype "passive"))
    )
    (net (code "85") (name "/~{SC_LOAD}") (class "Default")
      (node (ref "E31") (pin "10") (pinfunction "O_10") (pintype "output"))
      (node (ref "E34") (pin "11") (pinfunction "LD_11") (pintype "input"))
      (node (ref "E37") (pin "11") (pinfunction "LD_11") (pintype "input"))
    )
    (net (code "86") (name "/~{TP3}") (class "Default")
      (node (ref "E25") (pin "2") (pinfunction "O_2") (pintype "output"))
      (node (ref "E30") (pin "4") (pinfunction "PRE_4") (pintype "input"))
      (node (ref "E8") (pin "8") (pinfunction "I0_8") (pintype "input"))
    )
    (net (code "87") (name "GND") (class "Default")
      (node (ref "C1") (pin "2") (pinfunction "2_2") (pintype "passive"))
      (node (ref "C10") (pin "2") (pinfunction "2_2") (pintype "passive"))
      (node (ref "C11") (pin "2") (pinfunction "2_2") (pintype "passive"))
      (node (ref "C12") (pin "2") (pinfunction "2_2") (pintype "passive"))
      (node (ref "C14") (pin "2") (pinfunction "2_2") (pintype "passive"))
      (node (ref "C15") (pin "2") (pinfunction "2_2") (pintype "passive"))
      (node (ref "C16") (pin "2") (pinfunction "2_2") (pintype "passive"))
      (node (ref "C17") (pin "2") (pinfunction "2_2") (pintype "passive"))
      (node (ref "C18") (pin "2") (pinfunction "2_2") (pintype "passive"))
      (node (ref "C19") (pin "2") (pinfunction "2_2") (pintype "passive"))
      (node (ref "C2") (pin "2") (pinfunction "2_2") (pintype "passive"))
      (node (ref "C20") (pin "2") (pinfunction "2_2") (pintype "passive"))
      (node (ref "C21") (pin "2") (pinfunction "2_2") (pintype "passive"))
      (node (ref "C22") (pin "2") (pinfunction "2_2") (pintype "passive"))
      (node (ref "C23") (pin "2") (pinfunction "2_2") (pintype "passive"))
      (node (ref "C24") (pin "2") (pinfunction "2_2") (pintype "passive"))
      (node (ref "C25") (pin "2") (pinfunction "2_2") (pintype "passive"))
      (node (ref "C26") (pin "2") (pinfunction "2_2") (pintype "passive"))
      (node (ref "C27") (pin "2") (pinfunction "2_2") (pintype "passive"))
      (node (ref "C28") (pin "2") (pinfunction "2_2") (pintype "passive"))
      (node (ref "C29") (pin "2") (pinfunction "2_2") (pintype "passive"))
      (node (ref "C3") (pin "2") (pinfunction "2_2") (pintype "passive"))
      (node (ref "C30") (pin "2") (pinfunction "2_2") (pintype "passive"))
      (node (ref "C31") (pin "2") (pinfunction "2_2") (pintype "passive"))
      (node (ref "C32") (pin "2") (pinfunction "2_2") (pintype "passive"))
      (node (ref "C33") (pin "2") (pinfunction "2_2") (pintype "passive"))
      (node (ref "C34") (pin "2") (pinfunction "2_2") (pintype "passive"))
      (node (ref "C35") (pin "-") (pinfunction "-_-") (pintype "passive"))
      (node (ref "C36") (pin "-") (pinfunction "-_-") (pintype "passive"))
      (node (ref "C37") (pin "-") (pinfunction "-_-") (pintype "passive"))
      (node (ref "C4") (pin "2") (pinfunction "2_2") (pintype "passive"))
      (node (ref "C6") (pin "2") (pinfunction "2_2") (pintype "passive"))
      (node (ref "C7") (pin "2") (pinfunction "2_2") (pintype "passive"))
      (node (ref "C8") (pin "2") (pinfunction "2_2") (pintype "passive"))
      (node (ref "C9") (pin "2") (pinfunction "2_2") (pintype "passive"))
      (node (ref "E17") (pin "10") (pinfunction "I1_10") (pintype "input"))
      (node (ref "E17") (pin "11") (pinfunction "I0_11") (pintype "input"))
      (node (ref "E17") (pin "4") (pinfunction "I0_4") (pintype "input"))
      (node (ref "E17") (pin "6") (pinfunction "I0_6") (pintype "input"))
      (node (ref "E20") (pin "10") (pinfunction "I1_10") (pintype "input"))
      (node (ref "E21") (pin "10") (pinfunction "I1_10") (pintype "input"))
      (node (ref "E21") (pin "12") (pinfunction "I1_12") (pintype "input"))
      (node (ref "E25") (pin "10") (pinfunction "I1_10") (pintype "input"))
      (node (ref "E25") (pin "7") (pinfunction "I1_7") (pintype "input"))
      (node (ref "E29") (pin "10") (pinfunction "I1_10") (pintype "input"))
      (node (ref "E29") (pin "12") (pinfunction "I1_12") (pintype "input"))
      (node (ref "E29") (pin "4") (pinfunction "I0_4") (pintype "input"))
      (node (ref "E29") (pin "6") (pinfunction "I0_6") (pintype "input"))
      (node (ref "E32") (pin "10") (pinfunction "I1_10") (pintype "input"))
      (node (ref "E32") (pin "12") (pinfunction "I1_12") (pintype "input"))
      (node (ref "E32") (pin "4") (pinfunction "I0_4") (pintype "input"))
      (node (ref "E32") (pin "6") (pinfunction "I0_6") (pintype "input"))
      (node (ref "E34") (pin "1") (pinfunction "B_1") (pintype "input"))
      (node (ref "E34") (pin "10") (pinfunction "C_10") (pintype "input"))
      (node (ref "E34") (pin "9") (pinfunction "D_9") (pintype "input"))
      (node (ref "E36") (pin "7") (pinfunction "S1_7") (pintype "input"))
      (node (ref "H") (pin "J2") (pinfunction "P_J2") (pintype "passive"))
      (node (ref "H") (pin "K2") (pinfunction "P_K2") (pintype "passive"))
      (node (ref "H") (pin "L2") (pinfunction "P_L2") (pintype "passive"))
      (node (ref "H") (pin "M2") (pinfunction "P_M2") (pintype "passive"))
      (node (ref "H") (pin "N2") (pinfunction "P_N2") (pintype "passive"))
      (node (ref "H") (pin "P2") (pinfunction "P_P2") (pintype "passive"))
      (node (ref "H") (pin "R2") (pinfunction "P_R2") (pintype "passive"))
      (node (ref "H") (pin "S2") (pinfunction "P_S2") (pintype "passive"))
      (node (ref "J") (pin "C1") (pinfunction "P_C1") (pintype "passive"))
      (node (ref "J") (pin "C2") (pinfunction "P_C2") (pintype "passive"))
      (node (ref "J") (pin "E1") (pinfunction "P_E1") (pintype "passive"))
      (node (ref "J") (pin "E2") (pinfunction "P_E2") (pintype "passive"))
      (node (ref "J") (pin "H1") (pinfunction "P_H1") (pintype "passive"))
      (node (ref "J") (pin "H2") (pinfunction "P_H2") (pintype "passive"))
      (node (ref "J") (pin "R1") (pinfunction "P_R1") (pintype "passive"))
      (node (ref "J") (pin "R2") (pinfunction "P_R2") (pintype "passive"))
      (node (ref "J") (pin "T1") (pinfunction "P_T1") (pintype "passive"))
      (node (ref "J") (pin "T2") (pinfunction "P_T2") (pintype "passive"))
      (node (ref "J") (pin "V1") (pinfunction "P_V1") (pintype "passive"))
      (node (ref "U$2") (pin "AC2") (pinfunction "1_AC2") (pintype "bidirectional"))
      (node (ref "U$2") (pin "AF1") (pinfunction "1_AF1") (pintype "bidirectional"))
      (node (ref "U$2") (pin "AF2") (pinfunction "1_AF2") (pintype "bidirectional"))
      (node (ref "U$2") (pin "AN1") (pinfunction "1_AN1") (pintype "bidirectional"))
      (node (ref "U$2") (pin "AN2") (pinfunction "1_AN2") (pintype "bidirectional"))
      (node (ref "U$2") (pin "AT1") (pinfunction "1_AT1") (pintype "bidirectional"))
      (node (ref "U$2") (pin "AT2") (pinfunction "1_AT2") (pintype "bidirectional"))
      (node (ref "U$2") (pin "BC1") (pinfunction "1_BC1") (pintype "bidirectional"))
      (node (ref "U$2") (pin "BC2") (pinfunction "1_BC2") (pintype "bidirectional"))
      (node (ref "U$2") (pin "BF1") (pinfunction "1_BF1") (pintype "bidirectional"))
      (node (ref "U$2") (pin "BF2") (pinfunction "1_BF2") (pintype "bidirectional"))
      (node (ref "U$2") (pin "BN1") (pinfunction "1_BN1") (pintype "bidirectional"))
      (node (ref "U$2") (pin "BN2") (pinfunction "1_BN2") (pintype "bidirectional"))
      (node (ref "U$2") (pin "BT1") (pinfunction "1_BT1") (pintype "bidirectional"))
      (node (ref "U$2") (pin "BT2") (pinfunction "1_BT2") (pintype "bidirectional"))
      (node (ref "U$2") (pin "CC1") (pinfunction "1_CC1") (pintype "bidirectional"))
      (node (ref "U$2") (pin "CC2") (pinfunction "1_CC2") (pintype "bidirectional"))
      (node (ref "U$2") (pin "CF1") (pinfunction "1_CF1") (pintype "bidirectional"))
      (node (ref "U$2") (pin "CF2") (pinfunction "1_CF2") (pintype "bidirectional"))
      (node (ref "U$2") (pin "CN1") (pinfunction "1_CN1") (pintype "bidirectional"))
      (node (ref "U$2") (pin "CN2") (pinfunction "1_CN2") (pintype "bidirectional"))
      (node (ref "U$2") (pin "CT1") (pinfunction "1_CT1") (pintype "bidirectional"))
      (node (ref "U$2") (pin "CT2") (pinfunction "1_CT2") (pintype "bidirectional"))
      (node (ref "U$2") (pin "DC1") (pinfunction "1_DC1") (pintype "bidirectional"))
      (node (ref "U$2") (pin "DC2") (pinfunction "1_DC2") (pintype "bidirectional"))
      (node (ref "U$2") (pin "DF1") (pinfunction "1_DF1") (pintype "bidirectional"))
      (node (ref "U$2") (pin "DF2") (pinfunction "1_DF2") (pintype "bidirectional"))
      (node (ref "U$2") (pin "DN1") (pinfunction "1_DN1") (pintype "bidirectional"))
      (node (ref "U$2") (pin "DN2") (pinfunction "1_DN2") (pintype "bidirectional"))
      (node (ref "U$2") (pin "DT1") (pinfunction "1_DT1") (pintype "bidirectional"))
      (node (ref "U$2") (pin "DT2") (pinfunction "1_DT2") (pintype "bidirectional"))
    )
    (net (code "88") (name "Net-(E1B-I1)") (class "Default")
      (node (ref "E1") (pin "6") (pinfunction "I1_6") (pintype "input"))
      (node (ref "E21") (pin "14") (pinfunction "O_14") (pintype "output"))
    )
    (net (code "89") (name "Net-(E1D-I0)") (class "Default")
      (node (ref "E1") (pin "11") (pinfunction "I0_11") (pintype "input"))
      (node (ref "E30") (pin "6") (pinfunction "~{Q}_6") (pintype "output"))
      (node (ref "E31") (pin "9") (pinfunction "I1_9") (pintype "input"))
    )
    (net (code "90") (name "Net-(E2A-I)") (class "Default")
      (node (ref "E2") (pin "1") (pinfunction "I_1") (pintype "input"))
      (node (ref "E7") (pin "8") (pinfunction "O_8") (pintype "output"))
    )
    (net (code "91") (name "Net-(E2E-O)") (class "Default")
      (node (ref "E2") (pin "10") (pinfunction "O_10") (pintype "output"))
      (node (ref "E4") (pin "9") (pinfunction "J_9") (pintype "input"))
    )
    (net (code "92") (name "Net-(E2F-O)") (class "Default")
      (node (ref "E2") (pin "12") (pinfunction "O_12") (pintype "output"))
      (node (ref "E4") (pin "12") (pinfunction "K_12") (pintype "input"))
    )
    (net (code "93") (name "Net-(E6A-~{Q})") (class "Default")
      (node (ref "E6") (pin "6") (pinfunction "~{Q}_6") (pintype "output"))
      (node (ref "E7") (pin "2") (pinfunction "I1_2") (pintype "input"))
    )
    (net (code "94") (name "Net-(E6B-~{Q})") (class "Default")
      (node (ref "E6") (pin "8") (pinfunction "~{Q}_8") (pintype "output"))
      (node (ref "E7") (pin "3") (pinfunction "I2_3") (pintype "input"))
    )
    (net (code "95") (name "Net-(E10A-~{Q})") (class "Default")
      (node (ref "E10") (pin "6") (pinfunction "~{Q}_6") (pintype "output"))
      (node (ref "E7") (pin "4") (pinfunction "I3_4") (pintype "input"))
    )
    (net (code "96") (name "Net-(E10B-~{Q})") (class "Default")
      (node (ref "E10") (pin "8") (pinfunction "~{Q}_8") (pintype "output"))
      (node (ref "E7") (pin "5") (pinfunction "I4_5") (pintype "input"))
    )
    (net (code "97") (name "Net-(E11A-A2)") (class "Default")
      (node (ref "E11") (pin "12") (pinfunction "A2_12") (pintype "input"))
      (node (ref "E19") (pin "12") (pinfunction "A2_12") (pintype "input"))
      (node (ref "E22") (pin "6") (pinfunction "~{Q}_6") (pintype "output"))
      (node (ref "E23") (pin "5") (pinfunction "I4_5") (pintype "input"))
    )
    (net (code "98") (name "Net-(E11A-A4)") (class "Default")
      (node (ref "E11") (pin "14") (pinfunction "A4_14") (pintype "input"))
      (node (ref "E19") (pin "15") (pinfunction "~{CE}_15") (pintype "input"))
      (node (ref "E3") (pin "8") (pinfunction "O_8") (pintype "output"))
    )
    (net (code "99") (name "Net-(E11A-~{CE})") (class "Default")
      (node (ref "E11") (pin "15") (pinfunction "~{CE}_15") (pintype "input"))
      (node (ref "E3") (pin "6") (pinfunction "O_6") (pintype "output"))
    )
    (net (code "100") (name "Net-(E14A-Q)") (class "Default")
      (node (ref "E14") (pin "5") (pinfunction "Q_5") (pintype "output"))
      (node (ref "E15") (pin "1") (pinfunction "I0_1") (pintype "input"))
      (node (ref "E23") (pin "1") (pinfunction "I0_1") (pintype "input"))
    )
    (net (code "101") (name "Net-(E14B-Q)") (class "Default")
      (node (ref "E14") (pin "9") (pinfunction "Q_9") (pintype "output"))
      (node (ref "E15") (pin "2") (pinfunction "I1_2") (pintype "input"))
      (node (ref "E23") (pin "2") (pinfunction "I1_2") (pintype "input"))
    )
    (net (code "102") (name "Net-(E15A-I2)") (class "Default")
      (node (ref "E15") (pin "3") (pinfunction "I2_3") (pintype "input"))
      (node (ref "E18") (pin "6") (pinfunction "~{Q}_6") (pintype "output"))
      (node (ref "E19") (pin "13") (pinfunction "A3_13") (pintype "input"))
      (node (ref "E28") (pin "9") (pinfunction "I0_9") (pintype "input"))
    )
    (net (code "103") (name "Net-(E15A-I3)") (class "Default")
      (node (ref "E15") (pin "4") (pinfunction "I3_4") (pintype "input"))
      (node (ref "E18") (pin "9") (pinfunction "Q_9") (pintype "output"))
    )
    (net (code "104") (name "Net-(E15A-I4)") (class "Default")
      (node (ref "E15") (pin "5") (pinfunction "I4_5") (pintype "input"))
      (node (ref "E22") (pin "5") (pinfunction "Q_5") (pintype "output"))
    )
    (net (code "105") (name "Net-(E16A-I)") (class "Default")
      (node (ref "E16") (pin "1") (pinfunction "I_1") (pintype "input"))
      (node (ref "E28") (pin "4") (pinfunction "I1_4") (pintype "input"))
      (node (ref "E35") (pin "2") (pinfunction "I0_2") (pintype "input"))
      (node (ref "E37") (pin "3") (pinfunction "QA_3") (pintype "output"))
    )
    (net (code "106") (name "Net-(E16A-O)") (class "Default")
      (node (ref "E16") (pin "2") (pinfunction "O_2") (pintype "output"))
      (node (ref "E24") (pin "3") (pinfunction "I0_3") (pintype "input"))
    )
    (net (code "107") (name "Net-(E16B-O)") (class "Default")
      (node (ref "E16") (pin "4") (pinfunction "O_4") (pintype "output"))
      (node (ref "E31") (pin "12") (pinfunction "I1_12") (pintype "input"))
    )
    (net (code "108") (name "Net-(E16C-I)") (class "Default")
      (node (ref "E16") (pin "5") (pinfunction "I_5") (pintype "input"))
      (node (ref "E27") (pin "8") (pinfunction "O_8") (pintype "output"))
    )
    (net (code "109") (name "Net-(E16C-O)") (class "Default")
      (node (ref "E1") (pin "2") (pinfunction "I0_2") (pintype "input"))
      (node (ref "E16") (pin "6") (pinfunction "O_6") (pintype "output"))
      (node (ref "E30") (pin "11") (pinfunction "CLK_11") (pintype "input"))
    )
    (net (code "110") (name "Net-(E16F-I)") (class "Default")
      (node (ref "E16") (pin "13") (pinfunction "I_13") (pintype "input"))
      (node (ref "E28") (pin "6") (pinfunction "O_6") (pintype "output"))
      (node (ref "E33") (pin "11") (pinfunction "I2_11") (pintype "input"))
      (node (ref "E33") (pin "13") (pinfunction "I2_13") (pintype "input"))
    )
    (net (code "111") (name "Net-(E17A-O)") (class "Default")
      (node (ref "E17") (pin "3") (pinfunction "O_3") (pintype "output"))
      (node (ref "E9") (pin "3") (pinfunction "I1_3") (pintype "input"))
    )
    (net (code "112") (name "Net-(E17B-O)") (class "Default")
      (node (ref "E1") (pin "3") (pinfunction "I1_3") (pintype "input"))
      (node (ref "E17") (pin "2") (pinfunction "O_2") (pintype "output"))
    )
    (net (code "113") (name "Net-(E17C-O)") (class "Default")
      (node (ref "E17") (pin "14") (pinfunction "O_14") (pintype "output"))
      (node (ref "E27") (pin "9") (pinfunction "I0_9") (pintype "input"))
    )
    (net (code "114") (name "Net-(E17D-O)") (class "Default")
      (node (ref "E17") (pin "13") (pinfunction "O_13") (pintype "output"))
      (node (ref "E27") (pin "10") (pinfunction "I1_10") (pintype "input"))
    )
    (net (code "115") (name "Net-(E18A-Q)") (class "Default")
      (node (ref "E18") (pin "5") (pinfunction "Q_5") (pintype "output"))
      (node (ref "E23") (pin "3") (pinfunction "I2_3") (pintype "input"))
    )
    (net (code "116") (name "Net-(E18B-~{Q})") (class "Default")
      (node (ref "E18") (pin "8") (pinfunction "~{Q}_8") (pintype "output"))
      (node (ref "E23") (pin "4") (pinfunction "I3_4") (pintype "input"))
    )
    (net (code "117") (name "Net-(E20C-O)") (class "Default")
      (node (ref "E20") (pin "14") (pinfunction "O_14") (pintype "output"))
      (node (ref "E4") (pin "8") (pinfunction "CLR_8") (pintype "input"))
    )
    (net (code "118") (name "Net-(E20D-O)") (class "Default")
      (node (ref "E20") (pin "13") (pinfunction "O_13") (pintype "output"))
      (node (ref "E30") (pin "12") (pinfunction "D_12") (pintype "input"))
    )
    (net (code "119") (name "Net-(E22B-Q)") (class "Default")
      (node (ref "E22") (pin "9") (pinfunction "Q_9") (pintype "output"))
      (node (ref "E23") (pin "6") (pinfunction "I5_6") (pintype "input"))
    )
    (net (code "120") (name "Net-(E23A-I6)") (class "Default")
      (node (ref "E23") (pin "11") (pinfunction "I6_11") (pintype "input"))
      (node (ref "E26") (pin "5") (pinfunction "Q_5") (pintype "output"))
    )
    (net (code "121") (name "Net-(E24B-I1)") (class "Default")
      (node (ref "E24") (pin "4") (pinfunction "I1_4") (pintype "input"))
      (node (ref "E31") (pin "4") (pinfunction "O_4") (pintype "output"))
    )
    (net (code "122") (name "Net-(E24B-I2)") (class "Default")
      (node (ref "E24") (pin "5") (pinfunction "I2_5") (pintype "input"))
      (node (ref "E31") (pin "1") (pinfunction "O_1") (pintype "output"))
      (node (ref "E33") (pin "10") (pinfunction "I1_10") (pintype "input"))
    )
    (net (code "123") (name "Net-(E25A-O)") (class "Default")
      (node (ref "E25") (pin "3") (pinfunction "O_3") (pintype "output"))
      (node (ref "E9") (pin "11") (pinfunction "I0_11") (pintype "input"))
      (node (ref "E9") (pin "12") (pinfunction "I1_12") (pintype "input"))
    )
    (net (code "124") (name "Net-(E26B-~{Q})") (class "Default")
      (node (ref "E26") (pin "8") (pinfunction "~{Q}_8") (pintype "output"))
      (node (ref "E7") (pin "6") (pinfunction "I5_6") (pintype "input"))
    )
    (net (code "125") (name "Net-(E27B-O)") (class "Default")
      (node (ref "E27") (pin "6") (pinfunction "O_6") (pintype "output"))
      (node (ref "E3") (pin "4") (pinfunction "I2_4") (pintype "input"))
    )
    (net (code "126") (name "Net-(E28A-O)") (class "Default")
      (node (ref "E28") (pin "12") (pinfunction "O_12") (pintype "output"))
      (node (ref "E4") (pin "6") (pinfunction "CLK_6") (pintype "input"))
    )
    (net (code "127") (name "Net-(E28B-I0)") (class "Default")
      (node (ref "E28") (pin "3") (pinfunction "I0_3") (pintype "input"))
      (node (ref "E31") (pin "5") (pinfunction "I0_5") (pintype "input"))
      (node (ref "E33") (pin "5") (pinfunction "I2_5") (pintype "input"))
      (node (ref "E35") (pin "9") (pinfunction "I1_9") (pintype "input"))
      (node (ref "E37") (pin "7") (pinfunction "QD_7") (pintype "output"))
    )
    (net (code "128") (name "Net-(E28B-I2)") (class "Default")
      (node (ref "E28") (pin "5") (pinfunction "I2_5") (pintype "input"))
      (node (ref "E31") (pin "6") (pinfunction "I1_6") (pintype "input"))
      (node (ref "E35") (pin "5") (pinfunction "I0_5") (pintype "input"))
      (node (ref "E37") (pin "2") (pinfunction "QB_2") (pintype "output"))
    )
    (net (code "129") (name "Net-(E31A-I0)") (class "Default")
      (node (ref "E31") (pin "2") (pinfunction "I0_2") (pintype "input"))
      (node (ref "E33") (pin "1") (pinfunction "I0_1") (pintype "input"))
      (node (ref "E34") (pin "3") (pinfunction "QA_3") (pintype "output"))
      (node (ref "E9") (pin "6") (pinfunction "I1_6") (pintype "input"))
    )
    (net (code "130") (name "Net-(E31A-I1)") (class "Default")
      (node (ref "E31") (pin "3") (pinfunction "I1_3") (pintype "input"))
      (node (ref "E33") (pin "2") (pinfunction "I1_2") (pintype "input"))
      (node (ref "E33") (pin "3") (pinfunction "I0_3") (pintype "input"))
      (node (ref "E35") (pin "12") (pinfunction "I1_12") (pintype "input"))
      (node (ref "E37") (pin "6") (pinfunction "QC_6") (pintype "output"))
    )
    (net (code "131") (name "Net-(E31C-I0)") (class "Default")
      (node (ref "E31") (pin "13") (pinfunction "O_13") (pintype "output"))
      (node (ref "E31") (pin "8") (pinfunction "I0_8") (pintype "input"))
    )
    (net (code "132") (name "Net-(E32A-O)") (class "Default")
      (node (ref "E32") (pin "3") (pinfunction "O_3") (pintype "output"))
      (node (ref "E36") (pin "1") (pinfunction "A0_1") (pintype "input"))
    )
    (net (code "133") (name "Net-(E32B-O)") (class "Default")
      (node (ref "E32") (pin "2") (pinfunction "O_2") (pintype "output"))
      (node (ref "E36") (pin "6") (pinfunction "A1_6") (pintype "input"))
    )
    (net (code "134") (name "Net-(E32C-O)") (class "Default")
      (node (ref "E32") (pin "14") (pinfunction "O_14") (pintype "output"))
      (node (ref "E36") (pin "15") (pinfunction "A3_15") (pintype "input"))
    )
    (net (code "135") (name "Net-(E32D-O)") (class "Default")
      (node (ref "E32") (pin "13") (pinfunction "O_13") (pintype "output"))
      (node (ref "E36") (pin "10") (pinfunction "A2_10") (pintype "input"))
    )
    (net (code "136") (name "Net-(E34A-A)") (class "Default")
      (node (ref "E34") (pin "15") (pinfunction "A_15") (pintype "input"))
      (node (ref "E9") (pin "1") (pinfunction "O_1") (pintype "open_collector"))
      (node (ref "E9") (pin "13") (pinfunction "O_13") (pintype "open_collector"))
      (node (ref "R10") (pin "1") (pinfunction "1_1") (pintype "passive"))
    )
    (net (code "137") (name "Net-(E34A-UP)") (class "Default")
      (node (ref "E34") (pin "5") (pinfunction "UP_5") (pintype "input"))
      (node (ref "E37") (pin "12") (pinfunction "CO_12") (pintype "output"))
    )
    (net (code "138") (name "Net-(E36A-F0)") (class "Default")
      (node (ref "E36") (pin "3") (pinfunction "F0_3") (pintype "output"))
      (node (ref "E37") (pin "9") (pinfunction "D_9") (pintype "input"))
    )
    (net (code "139") (name "Net-(E36A-F1)") (class "Default")
      (node (ref "E36") (pin "4") (pinfunction "F1_4") (pintype "output"))
      (node (ref "E37") (pin "10") (pinfunction "C_10") (pintype "input"))
    )
    (net (code "140") (name "Net-(E36A-F2)") (class "Default")
      (node (ref "E36") (pin "12") (pinfunction "F2_12") (pintype "output"))
      (node (ref "E37") (pin "1") (pinfunction "B_1") (pintype "input"))
    )
    (net (code "141") (name "Net-(E36A-F3)") (class "Default")
      (node (ref "E36") (pin "13") (pinfunction "F3_13") (pintype "output"))
      (node (ref "E37") (pin "15") (pinfunction "A_15") (pintype "input"))
    )
    (net (code "142") (name "VCC") (class "Default")
      (node (ref "C1") (pin "1") (pinfunction "1_1") (pintype "passive"))
      (node (ref "C10") (pin "1") (pinfunction "1_1") (pintype "passive"))
      (node (ref "C11") (pin "1") (pinfunction "1_1") (pintype "passive"))
      (node (ref "C12") (pin "1") (pinfunction "1_1") (pintype "passive"))
      (node (ref "C14") (pin "1") (pinfunction "1_1") (pintype "passive"))
      (node (ref "C15") (pin "1") (pinfunction "1_1") (pintype "passive"))
      (node (ref "C16") (pin "1") (pinfunction "1_1") (pintype "passive"))
      (node (ref "C17") (pin "1") (pinfunction "1_1") (pintype "passive"))
      (node (ref "C18") (pin "1") (pinfunction "1_1") (pintype "passive"))
      (node (ref "C19") (pin "1") (pinfunction "1_1") (pintype "passive"))
      (node (ref "C2") (pin "1") (pinfunction "1_1") (pintype "passive"))
      (node (ref "C20") (pin "1") (pinfunction "1_1") (pintype "passive"))
      (node (ref "C21") (pin "1") (pinfunction "1_1") (pintype "passive"))
      (node (ref "C22") (pin "1") (pinfunction "1_1") (pintype "passive"))
      (node (ref "C23") (pin "1") (pinfunction "1_1") (pintype "passive"))
      (node (ref "C24") (pin "1") (pinfunction "1_1") (pintype "passive"))
      (node (ref "C25") (pin "1") (pinfunction "1_1") (pintype "passive"))
      (node (ref "C26") (pin "1") (pinfunction "1_1") (pintype "passive"))
      (node (ref "C27") (pin "1") (pinfunction "1_1") (pintype "passive"))
      (node (ref "C28") (pin "1") (pinfunction "1_1") (pintype "passive"))
      (node (ref "C29") (pin "1") (pinfunction "1_1") (pintype "passive"))
      (node (ref "C3") (pin "1") (pinfunction "1_1") (pintype "passive"))
      (node (ref "C30") (pin "1") (pinfunction "1_1") (pintype "passive"))
      (node (ref "C31") (pin "1") (pinfunction "1_1") (pintype "passive"))
      (node (ref "C32") (pin "1") (pinfunction "1_1") (pintype "passive"))
      (node (ref "C33") (pin "1") (pinfunction "1_1") (pintype "passive"))
      (node (ref "C34") (pin "1") (pinfunction "1_1") (pintype "passive"))
      (node (ref "C35") (pin "+") (pinfunction "+_+") (pintype "passive"))
      (node (ref "C36") (pin "+") (pinfunction "+_+") (pintype "passive"))
      (node (ref "C37") (pin "+") (pinfunction "+_+") (pintype "passive"))
      (node (ref "C4") (pin "1") (pinfunction "1_1") (pintype "passive"))
      (node (ref "C6") (pin "1") (pinfunction "1_1") (pintype "passive"))
      (node (ref "C7") (pin "1") (pinfunction "1_1") (pintype "passive"))
      (node (ref "C8") (pin "1") (pinfunction "1_1") (pintype "passive"))
      (node (ref "C9") (pin "1") (pinfunction "1_1") (pintype "passive"))
      (node (ref "R1") (pin "2") (pinfunction "2_2") (pintype "passive"))
      (node (ref "R10") (pin "2") (pinfunction "2_2") (pintype "passive"))
      (node (ref "R11") (pin "2") (pinfunction "2_2") (pintype "passive"))
      (node (ref "R13") (pin "2") (pinfunction "2_2") (pintype "passive"))
      (node (ref "R2") (pin "2") (pinfunction "2_2") (pintype "passive"))
      (node (ref "R3") (pin "2") (pinfunction "2_2") (pintype "passive"))
      (node (ref "R4") (pin "2") (pinfunction "2_2") (pintype "passive"))
      (node (ref "R5") (pin "2") (pinfunction "2_2") (pintype "passive"))
      (node (ref "R6") (pin "2") (pinfunction "2_2") (pintype "passive"))
      (node (ref "R7") (pin "2") (pinfunction "2_2") (pintype "passive"))
      (node (ref "R8") (pin "2") (pinfunction "2_2") (pintype "passive"))
      (node (ref "R9") (pin "2") (pinfunction "2_2") (pintype "passive"))
      (node (ref "U$2") (pin "AA2") (pinfunction "1_AA2") (pintype "bidirectional"))
      (node (ref "U$2") (pin "BA2") (pinfunction "1_BA2") (pintype "bidirectional"))
      (node (ref "U$2") (pin "CA2") (pinfunction "1_CA2") (pintype "bidirectional"))
    )
    (net (code "143") (name "unconnected-(E4B-Q-Pad11)") (class "Default")
      (node (ref "E4") (pin "11") (pinfunction "Q_11") (pintype "output"))
    )
    (net (code "144") (name "unconnected-(E6A-Q-Pad5)") (class "Default")
      (node (ref "E6") (pin "5") (pinfunction "Q_5") (pintype "output"))
    )
    (net (code "145") (name "unconnected-(E6B-Q-Pad9)") (class "Default")
      (node (ref "E6") (pin "9") (pinfunction "Q_9") (pintype "output"))
    )
    (net (code "146") (name "unconnected-(E10A-Q-Pad5)") (class "Default")
      (node (ref "E10") (pin "5") (pinfunction "Q_5") (pintype "output"))
    )
    (net (code "147") (name "unconnected-(E10B-Q-Pad9)") (class "Default")
      (node (ref "E10") (pin "9") (pinfunction "Q_9") (pintype "output"))
    )
    (net (code "148") (name "unconnected-(E14A-~{Q}-Pad6)") (class "Default")
      (node (ref "E14") (pin "6") (pinfunction "~{Q}_6") (pintype "output"))
    )
    (net (code "149") (name "unconnected-(E14B-~{Q}-Pad8)") (class "Default")
      (node (ref "E14") (pin "8") (pinfunction "~{Q}_8") (pintype "output"))
    )
    (net (code "150") (name "unconnected-(E26B-Q-Pad9)") (class "Default")
      (node (ref "E26") (pin "9") (pinfunction "Q_9") (pintype "output"))
    )
    (net (code "151") (name "unconnected-(E30A-Q-Pad5)") (class "Default")
      (node (ref "E30") (pin "5") (pinfunction "Q_5") (pintype "output"))
    )
    (net (code "152") (name "unconnected-(E34A-BO-Pad13)") (class "Default")
      (node (ref "E34") (pin "13") (pinfunction "BO_13") (pintype "output"))
    )
    (net (code "153") (name "unconnected-(E34A-CO-Pad12)") (class "Default")
      (node (ref "E34") (pin "12") (pinfunction "CO_12") (pintype "output"))
    )
    (net (code "154") (name "unconnected-(E34A-QB-Pad2)") (class "Default")
      (node (ref "E34") (pin "2") (pinfunction "QB_2") (pintype "output"))
    )
    (net (code "155") (name "unconnected-(E34A-QC-Pad6)") (class "Default")
      (node (ref "E34") (pin "6") (pinfunction "QC_6") (pintype "output"))
    )
    (net (code "156") (name "unconnected-(E34A-QD-Pad7)") (class "Default")
      (node (ref "E34") (pin "7") (pinfunction "QD_7") (pintype "output"))
    )
    (net (code "157") (name "unconnected-(E37A-BO-Pad13)") (class "Default")
      (node (ref "E37") (pin "13") (pinfunction "BO_13") (pintype "output"))
    )
  )
)
